# DCDC.net
KiCad netlist of a schematic drawn in Altium Designer
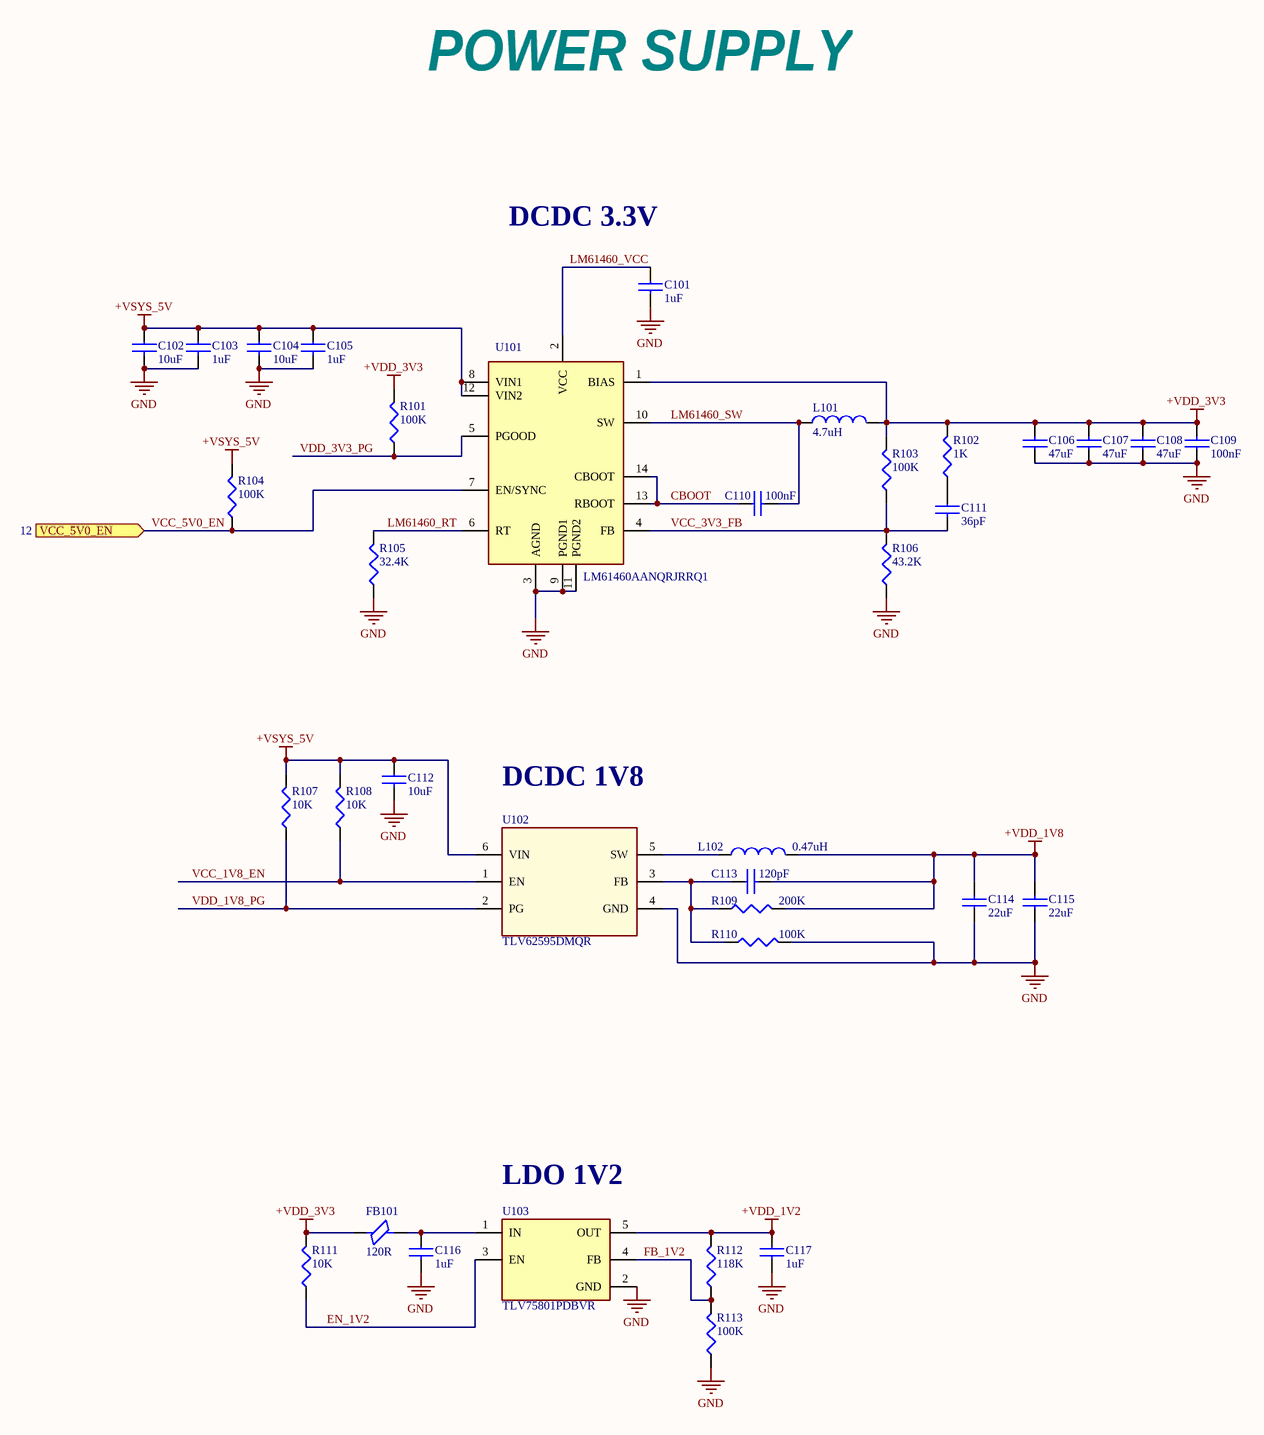
[diagram p0: DCDC.SchDoc]

(export (version "E")
  (design (tool "Eeschema 10.0.6"))
  (components
    (comp (ref "C101")
      (value "1uF")
      (footprint "C0603")
      (description "Multilayer Ceramic Capacitor, 1 uF, 16 V, ± 10%, X5R, 0603 [1608 Metric]")
      (fields
        (field (name "MANUFACTURER") "TDK")
        (field (name "MANUFACTURER PART NUMBER") "CGA3E1X5R1C105K080AC")
      )
      (libsource (lib "Schlib SOM AM625") (part "CGA3E1X5R1C105K080AC"))
    )
    (comp (ref "C102")
      (value "10uF")
      (footprint "C1206B/3216MM")
      (description "Multilayer Ceramic Capacitor, 10 uF, 16 V, ± 10%, X5R, 1206 [3216 Metric]")
      (fields
        (field (name "MANUFACTURER") "TDK")
        (field (name "MANUFACTURER PART NUMBER") "C3216X5R1C106K160AA")
      )
      (libsource (lib "Schlib SOM AM625") (part "C3216X5R1C106K160AA"))
    )
    (comp (ref "C103")
      (value "1uF")
      (footprint "C0603")
      (description "Multilayer Ceramic Capacitor, 1 uF, 16 V, ± 10%, X5R, 0603 [1608 Metric]")
      (fields
        (field (name "MANUFACTURER") "TDK")
        (field (name "MANUFACTURER PART NUMBER") "CGA3E1X5R1C105K080AC")
      )
      (libsource (lib "Schlib SOM AM625") (part "CGA3E1X5R1C105K080AC"))
    )
    (comp (ref "C104")
      (value "10uF")
      (footprint "C1206B/3216MM")
      (description "Multilayer Ceramic Capacitor, 10 uF, 16 V, ± 10%, X5R, 1206 [3216 Metric]")
      (fields
        (field (name "MANUFACTURER") "TDK")
        (field (name "MANUFACTURER PART NUMBER") "C3216X5R1C106K160AA")
      )
      (libsource (lib "Schlib SOM AM625") (part "C3216X5R1C106K160AA"))
    )
    (comp (ref "C105")
      (value "1uF")
      (footprint "C0603")
      (description "Multilayer Ceramic Capacitor, 1 uF, 16 V, ± 10%, X5R, 0603 [1608 Metric]")
      (fields
        (field (name "MANUFACTURER") "TDK")
        (field (name "MANUFACTURER PART NUMBER") "CGA3E1X5R1C105K080AC")
      )
      (libsource (lib "Schlib SOM AM625") (part "CGA3E1X5R1C105K080AC"))
    )
    (comp (ref "C106")
      (value "47uF")
      (footprint "C1206B/3216MM")
      (description "Multilayer Ceramic Capacitor, 47 uF, 16 V, ± 20%, X5R, 1206 [3216 Metric]")
      (fields
        (field (name "MANUFACTURER") "TDK")
        (field (name "MANUFACTURER PART NUMBER") "C3216X5R1C476M160AB")
      )
      (libsource (lib "Schlib SOM AM625") (part "C3216X5R1C476M160AB"))
    )
    (comp (ref "C107")
      (value "47uF")
      (footprint "C1206B/3216MM")
      (description "Multilayer Ceramic Capacitor, 47 uF, 16 V, ± 20%, X5R, 1206 [3216 Metric]")
      (fields
        (field (name "MANUFACTURER") "TDK")
        (field (name "MANUFACTURER PART NUMBER") "C3216X5R1C476M160AB")
      )
      (libsource (lib "Schlib SOM AM625") (part "C3216X5R1C476M160AB"))
    )
    (comp (ref "C108")
      (value "47uF")
      (footprint "C1206B/3216MM")
      (description "Multilayer Ceramic Capacitor, 47 uF, 16 V, ± 20%, X5R, 1206 [3216 Metric]")
      (fields
        (field (name "MANUFACTURER") "TDK")
        (field (name "MANUFACTURER PART NUMBER") "C3216X5R1C476M160AB")
      )
      (libsource (lib "Schlib SOM AM625") (part "C3216X5R1C476M160AB"))
    )
    (comp (ref "C109")
      (value "100nF")
      (footprint "C0603")
      (description "Multilayer Ceramic Capacitor, 0.1 uF, 25 V, ± 10%, X7R, 0603 [1608 Metric]")
      (fields
        (field (name "MANUFACTURER") "TDK")
        (field (name "MANUFACTURER PART NUMBER") "C1608X7R1E104K080AA")
      )
      (libsource (lib "Schlib SOM AM625") (part "C1608X7R1E104K080AA"))
    )
    (comp (ref "C110")
      (value "100nF")
      (footprint "C0603")
      (description "Multilayer Ceramic Capacitor, 0.1 uF, 25 V, ± 10%, X7R, 0603 [1608 Metric]")
      (fields
        (field (name "MANUFACTURER") "TDK")
        (field (name "MANUFACTURER PART NUMBER") "C1608X7R1E104K080AA")
      )
      (libsource (lib "Schlib SOM AM625") (part "C1608X7R1E104K080AA"))
    )
    (comp (ref "C111")
      (value "36pF")
      (footprint "C0402")
      (description "Capacitor Ceramic 36pF 50V C0G 1% 0402 Paper T/R")
      (fields
        (field (name "MANUFACTURER") "Yageo")
        (field (name "MANUFACTURER PART NUMBER") "CC0402FRNPO9BN360")
      )
      (libsource (lib "Schlib SOM AM625") (part "CC0402FRNPO9BN360"))
    )
    (comp (ref "C112")
      (value "10uF")
      (footprint "C0603")
      (description "Multilayer Ceramic Capacitor, 10 uF, 10 V, ± 10%, X5R, 0603 [1608 Metric]")
      (fields
        (field (name "MANUFACTURER") "TDK")
        (field (name "MANUFACTURER PART NUMBER") "C1608X5R1A106K080AC")
      )
      (libsource (lib "Schlib SOM AM625") (part "C1608X5R1A106K080AC"))
    )
    (comp (ref "C113")
      (value "120pF")
      (footprint "C0402")
      (description "Cap Ceramic 120pF 25V C0G 5% SMD 0402 125°C Paper T/R")
      (fields
        (field (name "MANUFACTURER") "KEMET")
        (field (name "MANUFACTURER PART NUMBER") "C0402C121J3GAC7867")
      )
      (libsource (lib "Schlib SOM AM625") (part "C0402C121J3GAC7867"))
    )
    (comp (ref "C114")
      (value "22uF")
      (footprint "C0805")
      (description "Multilayer Ceramic Capacitor, 22 uF, 25 V, ± 20%, X6S, 0805 [2012 Metric]")
      (fields
        (field (name "MANUFACTURER") "Yageo")
        (field (name "MANUFACTURER PART NUMBER") "CC0805MKX5R8BB226")
      )
      (libsource (lib "Schlib SOM AM625") (part "CC0805MKX5R8BB226"))
    )
    (comp (ref "C115")
      (value "22uF")
      (footprint "C0805")
      (description "Multilayer Ceramic Capacitor, 22 uF, 25 V, ± 20%, X6S, 0805 [2012 Metric]")
      (fields
        (field (name "MANUFACTURER") "Yageo")
        (field (name "MANUFACTURER PART NUMBER") "CC0805MKX5R8BB226")
      )
      (libsource (lib "Schlib SOM AM625") (part "CC0805MKX5R8BB226"))
    )
    (comp (ref "C116")
      (value "1uF")
      (footprint "C0402")
      (description "Multilayer Ceramic Capacitor, 1 uF, 16 V, ± 20%, C0G (NP0), 0201 [0603 Metric]")
      (fields
        (field (name "MANUFACTURER") "Yageo")
        (field (name "MANUFACTURER PART NUMBER") "CC0402KRX5R6BB105")
      )
      (libsource (lib "Schlib SOM AM625") (part "CC0402KRX5R6BB105"))
    )
    (comp (ref "C117")
      (value "1uF")
      (footprint "C0402")
      (description "Multilayer Ceramic Capacitor, 1 uF, 16 V, ± 20%, C0G (NP0), 0201 [0603 Metric]")
      (fields
        (field (name "MANUFACTURER") "Yageo")
        (field (name "MANUFACTURER PART NUMBER") "CC0402KRX5R6BB105")
      )
      (libsource (lib "Schlib SOM AM625") (part "CC0402KRX5R6BB105"))
    )
    (comp (ref "FB101")
      (value "120R")
      (footprint "FB0402")
      (description "Ferrite Beads Multi-Layer 120Ohm 25% 100MHz 1.3A 0.09Ohm DCR 0402 Automotive T/R")
      (fields
        (field (name "MANUFACTURER") "Murata")
        (field (name "MANUFACTURER PART NUMBER") "BLM15PD121SZ1D")
      )
      (libsource (lib "Schlib SOM AM625") (part "BLM15PD121SZ1D"))
    )
    (comp (ref "L101")
      (value "4.7uH")
      (footprint "IND_WE-XHMI_8080_WRE")
      (description "Fixed Ind 4.7UH 9.5A 8.65 Mohm")
      (fields
        (field (name "MANUFACTURER") "Wurth Electronics")
        (field (name "MANUFACTURER PART NUMBER") "74439358047")
      )
      (libsource (lib "Schlib SOM AM625") (part "74439358047"))
    )
    (comp (ref "L102")
      (value "0.47uH")
      (footprint "l2016")
      (description "Inductor Power Shielded Wirewound 0.47uH 20% 1MHz Metal 3.6A 0.032Ohm DCR 0806 T/R")
      (fields
        (field (name "MANUFACTURER") "Murata")
        (field (name "MANUFACTURER PART NUMBER") "DFE201610E-R47M=P2")
      )
      (libsource (lib "Schlib SOM AM625") (part "DFE201610E-R47M=P2"))
    )
    (comp (ref "R101")
      (value "100K")
      (footprint "R0402")
      (description "SMD Chip Resistor, 100 kOhm, ± 1%, 63 mW, 0402 [1005 Metric], Thick Film, General Purpose")
      (fields
        (field (name "MANUFACTURER") "Yageo")
        (field (name "MANUFACTURER PART NUMBER") "RC0402FR-07100KL")
      )
      (libsource (lib "Schlib SOM AM625") (part "RC0402FR-07100KL"))
    )
    (comp (ref "R102")
      (value "1K")
      (footprint "R0402")
      (description "SMD Chip Resistor, 1 kOhm, ± 1%, 63 mW, 0402 [1005 Metric], Thick Film, General Purpose")
      (fields
        (field (name "MANUFACTURER") "Yageo")
        (field (name "MANUFACTURER PART NUMBER") "RC0402FR-071KL")
      )
      (libsource (lib "Schlib SOM AM625") (part "RC0402FR-071KL"))
    )
    (comp (ref "R103")
      (value "100K")
      (footprint "R0402")
      (description "SMD Chip Resistor, 100 kOhm, ± 1%, 63 mW, 0402 [1005 Metric], Thick Film, General Purpose")
      (fields
        (field (name "MANUFACTURER") "Yageo")
        (field (name "MANUFACTURER PART NUMBER") "RC0402FR-07100KL")
      )
      (libsource (lib "Schlib SOM AM625") (part "RC0402FR-07100KL"))
    )
    (comp (ref "R104")
      (value "100K")
      (footprint "R0402")
      (description "SMD Chip Resistor, 100 kOhm, ± 1%, 63 mW, 0402 [1005 Metric], Thick Film, General Purpose")
      (fields
        (field (name "MANUFACTURER") "Yageo")
        (field (name "MANUFACTURER PART NUMBER") "RC0402FR-07100KL")
      )
      (libsource (lib "Schlib SOM AM625") (part "RC0402FR-07100KL"))
    )
    (comp (ref "R105")
      (value "32.4K")
      (footprint "R0402")
      (description "SMD Chip Resistor, 32.4 kOhm, ± 1%, 63 mW, 0402 [1005 Metric], Thick Film, General Purpose")
      (fields
        (field (name "MANUFACTURER") "Yageo")
        (field (name "MANUFACTURER PART NUMBER") "RC0402FR-0732K4L")
      )
      (libsource (lib "Schlib SOM AM625") (part "RC0402FR-0732K4L"))
    )
    (comp (ref "R106")
      (value "43.2K")
      (footprint "R0402")
      (description "SMD Chip Resistor, 43.2 kOhm, ± 1%, 63 mW, 0402 [1005 Metric], Thick Film, General Purpose")
      (fields
        (field (name "MANUFACTURER") "Yageo")
        (field (name "MANUFACTURER PART NUMBER") "RC0402FR-0743K2L")
      )
      (libsource (lib "Schlib SOM AM625") (part "RC0402FR-0743K2L"))
    )
    (comp (ref "R107")
      (value "10K")
      (footprint "R0402")
      (description "RES 10.0K OHM 1/16W 1% 0402 SMD")
      (fields
        (field (name "MANUFACTURER") "Yageo")
        (field (name "MANUFACTURER PART NUMBER") "RC0402FR-0710KL")
      )
      (libsource (lib "Schlib SOM AM625") (part "RC0402FR-0710KL"))
    )
    (comp (ref "R108")
      (value "10K")
      (footprint "R0402")
      (description "RES 10.0K OHM 1/16W 1% 0402 SMD")
      (fields
        (field (name "MANUFACTURER") "Yageo")
        (field (name "MANUFACTURER PART NUMBER") "RC0402FR-0710KL")
      )
      (libsource (lib "Schlib SOM AM625") (part "RC0402FR-0710KL"))
    )
    (comp (ref "R109")
      (value "200K")
      (footprint "R0402")
      (description "SMD Chip Resistor, 200 kOhm, ± 1%, 63 mW, 0402 [1005 Metric], Thick Film, General Purpose")
      (fields
        (field (name "MANUFACTURER") "Yageo")
        (field (name "MANUFACTURER PART NUMBER") "RC0402FR-07200KL")
      )
      (libsource (lib "Schlib SOM AM625") (part "RC0402FR-07200KL"))
    )
    (comp (ref "R110")
      (value "100K")
      (footprint "R0402")
      (description "SMD Chip Resistor, 100 kOhm, ± 1%, 63 mW, 0402 [1005 Metric], Thick Film, General Purpose")
      (fields
        (field (name "MANUFACTURER") "Yageo")
        (field (name "MANUFACTURER PART NUMBER") "AC0402FR-07100KL")
      )
      (libsource (lib "Schlib SOM AM625") (part "AC0402FR-07100KL"))
    )
    (comp (ref "R111")
      (value "10K")
      (footprint "R0402")
      (description "RES 10.0K OHM 1/16W 1% 0402 SMD")
      (fields
        (field (name "MANUFACTURER") "Yageo")
        (field (name "MANUFACTURER PART NUMBER") "RC0402FR-0710KL")
      )
      (libsource (lib "Schlib SOM AM625") (part "RC0402FR-0710KL"))
    )
    (comp (ref "R112")
      (value "118K")
      (footprint "R0402")
      (description "SMD Chip Resistor, 118 kOhm, ± 1%, 63 mW, 0402 [1005 Metric], Thick Film, General Purpose")
      (fields
        (field (name "MANUFACTURER") "Yageo")
        (field (name "MANUFACTURER PART NUMBER") "RC0402FR-07118KL")
      )
      (libsource (lib "Schlib SOM AM625") (part "RC0402FR-07118KL"))
    )
    (comp (ref "R113")
      (value "100K")
      (footprint "R0402")
      (description "SMD Chip Resistor, 100 kOhm, ± 1%, 63 mW, 0402 [1005 Metric], Thick Film, General Purpose")
      (fields
        (field (name "MANUFACTURER") "Yageo")
        (field (name "MANUFACTURER PART NUMBER") "AC0402FR-07100KL")
      )
      (libsource (lib "Schlib SOM AM625") (part "AC0402FR-07100KL"))
    )
    (comp (ref "U101")
      (value "LM61460AANQRJRRQ1")
      (footprint "14-VFQFN")
      (description "Automotive 3-V to 36-V, 6-A, low-noise synchronous step-down converter 14-VQFN-HR -40 to 150")
      (fields (field (name "MANUFACTURER") "Texas Instruments"))
      (libsource (lib "Schlib SOM AM625") (part "LM61460AANQRJRRQ1"))
    )
    (comp (ref "U102")
      (value "TLV62595DMQR")
      (footprint "VSON6_0D5_1D5X1D5X1MM")
      (fields (field (name "MANUFACTURER") "Texas Instruments"))
      (libsource (lib "Schlib SOM AM625") (part "TLV62595DMQR"))
    )
    (comp (ref "U103")
      (value "TLV75801PDBVR")
      (footprint "SOT23-5")
      (description "Adjustable 500-mA low-dropout (LDO) regulator 5-SOT-23 -40 to 125")
      (fields (field (name "MANUFACTURER") "Texas Instruments"))
      (libsource (lib "Schlib SOM AM625") (part "TLV75801PDBVR"))
    )
  )
  (nets
    (net (code "1") (name "+VDD_1V2") (class "Default")
      (node (ref "C117") (pin "1") (pinfunction "1_1") (pintype "passive"))
      (node (ref "R112") (pin "2") (pinfunction "2_2") (pintype "passive"))
      (node (ref "U103") (pin "5") (pinfunction "OUT_5") (pintype "passive"))
    )
    (net (code "2") (name "+VDD_1V8") (class "Default")
      (node (ref "C113") (pin "2") (pinfunction "2_2") (pintype "passive"))
      (node (ref "C114") (pin "2") (pinfunction "2_2") (pintype "passive"))
      (node (ref "C115") (pin "2") (pinfunction "2_2") (pintype "passive"))
      (node (ref "L102") (pin "2") (pinfunction "2_2") (pintype "passive"))
      (node (ref "R109") (pin "2") (pinfunction "2_2") (pintype "passive"))
    )
    (net (code "3") (name "+VDD_3V3") (class "Default")
      (node (ref "C106") (pin "2") (pinfunction "2_2") (pintype "passive"))
      (node (ref "C107") (pin "2") (pinfunction "2_2") (pintype "passive"))
      (node (ref "C108") (pin "2") (pinfunction "2_2") (pintype "passive"))
      (node (ref "C109") (pin "2") (pinfunction "2_2") (pintype "passive"))
      (node (ref "FB101") (pin "1") (pinfunction "1_1") (pintype "passive"))
      (node (ref "L101") (pin "2") (pinfunction "2_2") (pintype "passive"))
      (node (ref "R101") (pin "2") (pinfunction "2_2") (pintype "passive"))
      (node (ref "R102") (pin "2") (pinfunction "2_2") (pintype "passive"))
      (node (ref "R103") (pin "2") (pinfunction "2_2") (pintype "passive"))
      (node (ref "R111") (pin "2") (pinfunction "2_2") (pintype "passive"))
      (node (ref "U101") (pin "1") (pinfunction "BIAS_1") (pintype "passive"))
    )
    (net (code "4") (name "+VSYS_5V") (class "Default")
      (node (ref "C102") (pin "1") (pinfunction "1_1") (pintype "passive"))
      (node (ref "C103") (pin "1") (pinfunction "1_1") (pintype "passive"))
      (node (ref "C104") (pin "1") (pinfunction "1_1") (pintype "passive"))
      (node (ref "C105") (pin "1") (pinfunction "1_1") (pintype "passive"))
      (node (ref "C112") (pin "1") (pinfunction "1_1") (pintype "passive"))
      (node (ref "R104") (pin "2") (pinfunction "2_2") (pintype "passive"))
      (node (ref "R107") (pin "2") (pinfunction "2_2") (pintype "passive"))
      (node (ref "R108") (pin "2") (pinfunction "2_2") (pintype "passive"))
      (node (ref "U101") (pin "12") (pinfunction "VIN2_12") (pintype "passive"))
      (node (ref "U101") (pin "8") (pinfunction "VIN1_8") (pintype "passive"))
      (node (ref "U102") (pin "6") (pinfunction "VIN_6") (pintype "power_in"))
    )
    (net (code "5") (name "/CBOOT") (class "Default")
      (node (ref "C110") (pin "1") (pinfunction "1_1") (pintype "passive"))
      (node (ref "U101") (pin "13") (pinfunction "RBOOT_13") (pintype "passive"))
      (node (ref "U101") (pin "14") (pinfunction "CBOOT_14") (pintype "passive"))
    )
    (net (code "6") (name "/EN_1V2") (class "Default")
      (node (ref "R111") (pin "1") (pinfunction "1_1") (pintype "passive"))
      (node (ref "U103") (pin "3") (pinfunction "EN_3") (pintype "passive"))
    )
    (net (code "7") (name "/FB_1V2") (class "Default")
      (node (ref "R112") (pin "1") (pinfunction "1_1") (pintype "passive"))
      (node (ref "R113") (pin "2") (pinfunction "2_2") (pintype "passive"))
      (node (ref "U103") (pin "4") (pinfunction "FB_4") (pintype "passive"))
    )
    (net (code "8") (name "/LM61460_RT") (class "Default")
      (node (ref "R105") (pin "2") (pinfunction "2_2") (pintype "passive"))
      (node (ref "U101") (pin "6") (pinfunction "RT_6") (pintype "passive"))
    )
    (net (code "9") (name "/LM61460_SW") (class "Default")
      (node (ref "C110") (pin "2") (pinfunction "2_2") (pintype "passive"))
      (node (ref "L101") (pin "1") (pinfunction "1_1") (pintype "passive"))
      (node (ref "U101") (pin "10") (pinfunction "SW_10") (pintype "passive"))
    )
    (net (code "10") (name "/LM61460_VCC") (class "Default")
      (node (ref "C101") (pin "1") (pinfunction "1_1") (pintype "passive"))
      (node (ref "U101") (pin "2") (pinfunction "VCC_2") (pintype "passive"))
    )
    (net (code "11") (name "/VCC_1V8_EN") (class "Default")
      (node (ref "R108") (pin "1") (pinfunction "1_1") (pintype "passive"))
      (node (ref "U102") (pin "1") (pinfunction "EN_1") (pintype "passive"))
    )
    (net (code "12") (name "/VCC_3V3_FB") (class "Default")
      (node (ref "C111") (pin "2") (pinfunction "2_2") (pintype "passive"))
      (node (ref "R103") (pin "1") (pinfunction "1_1") (pintype "passive"))
      (node (ref "R106") (pin "2") (pinfunction "2_2") (pintype "passive"))
      (node (ref "U101") (pin "4") (pinfunction "FB_4") (pintype "passive"))
    )
    (net (code "13") (name "/VCC_5V0_EN") (class "Default")
      (node (ref "R104") (pin "1") (pinfunction "1_1") (pintype "passive"))
      (node (ref "U101") (pin "7") (pinfunction "EN/SYNC_7") (pintype "passive"))
    )
    (net (code "14") (name "/VDD_1V8_PG") (class "Default")
      (node (ref "R107") (pin "1") (pinfunction "1_1") (pintype "passive"))
      (node (ref "U102") (pin "2") (pinfunction "PG_2") (pintype "open_collector"))
    )
    (net (code "15") (name "/VDD_3V3_PG") (class "Default")
      (node (ref "R101") (pin "1") (pinfunction "1_1") (pintype "passive"))
      (node (ref "U101") (pin "5") (pinfunction "PGOOD_5") (pintype "passive"))
    )
    (net (code "16") (name "GND") (class "Default")
      (node (ref "C101") (pin "2") (pinfunction "2_2") (pintype "passive"))
      (node (ref "C102") (pin "2") (pinfunction "2_2") (pintype "passive"))
      (node (ref "C103") (pin "2") (pinfunction "2_2") (pintype "passive"))
      (node (ref "C104") (pin "2") (pinfunction "2_2") (pintype "passive"))
      (node (ref "C105") (pin "2") (pinfunction "2_2") (pintype "passive"))
      (node (ref "C106") (pin "1") (pinfunction "1_1") (pintype "passive"))
      (node (ref "C107") (pin "1") (pinfunction "1_1") (pintype "passive"))
      (node (ref "C108") (pin "1") (pinfunction "1_1") (pintype "passive"))
      (node (ref "C109") (pin "1") (pinfunction "1_1") (pintype "passive"))
      (node (ref "C112") (pin "2") (pinfunction "2_2") (pintype "passive"))
      (node (ref "C114") (pin "1") (pinfunction "1_1") (pintype "passive"))
      (node (ref "C115") (pin "1") (pinfunction "1_1") (pintype "passive"))
      (node (ref "C116") (pin "2") (pinfunction "2_2") (pintype "passive"))
      (node (ref "C117") (pin "2") (pinfunction "2_2") (pintype "passive"))
      (node (ref "R105") (pin "1") (pinfunction "1_1") (pintype "passive"))
      (node (ref "R106") (pin "1") (pinfunction "1_1") (pintype "passive"))
      (node (ref "R110") (pin "2") (pinfunction "2_2") (pintype "passive"))
      (node (ref "R113") (pin "1") (pinfunction "1_1") (pintype "passive"))
      (node (ref "U101") (pin "11") (pinfunction "PGND2_11") (pintype "passive"))
      (node (ref "U101") (pin "3") (pinfunction "AGND_3") (pintype "passive"))
      (node (ref "U101") (pin "9") (pinfunction "PGND1_9") (pintype "passive"))
      (node (ref "U102") (pin "4") (pinfunction "GND_4") (pintype "power_in"))
      (node (ref "U103") (pin "2") (pinfunction "GND_2") (pintype "power_in"))
    )
    (net (code "17") (name "Net-(C111-Pad1)") (class "Default")
      (node (ref "C111") (pin "1") (pinfunction "1_1") (pintype "passive"))
      (node (ref "R102") (pin "1") (pinfunction "1_1") (pintype "passive"))
    )
    (net (code "18") (name "Net-(U102-FB)") (class "Default")
      (node (ref "C113") (pin "1") (pinfunction "1_1") (pintype "passive"))
      (node (ref "R109") (pin "1") (pinfunction "1_1") (pintype "passive"))
      (node (ref "R110") (pin "1") (pinfunction "1_1") (pintype "passive"))
      (node (ref "U102") (pin "3") (pinfunction "FB_3") (pintype "passive"))
    )
    (net (code "19") (name "Net-(U102-SW)") (class "Default")
      (node (ref "L102") (pin "1") (pinfunction "1_1") (pintype "passive"))
      (node (ref "U102") (pin "5") (pinfunction "SW_5") (pintype "passive"))
    )
    (net (code "20") (name "Net-(U103-IN)") (class "Default")
      (node (ref "C116") (pin "1") (pinfunction "1_1") (pintype "passive"))
      (node (ref "FB101") (pin "2") (pinfunction "2_2") (pintype "passive"))
      (node (ref "U103") (pin "1") (pinfunction "IN_1") (pintype "passive"))
    )
  )
)
